# v1_2024-09-18.net
KiCad netlist of a schematic drawn in EasyEDA Pro
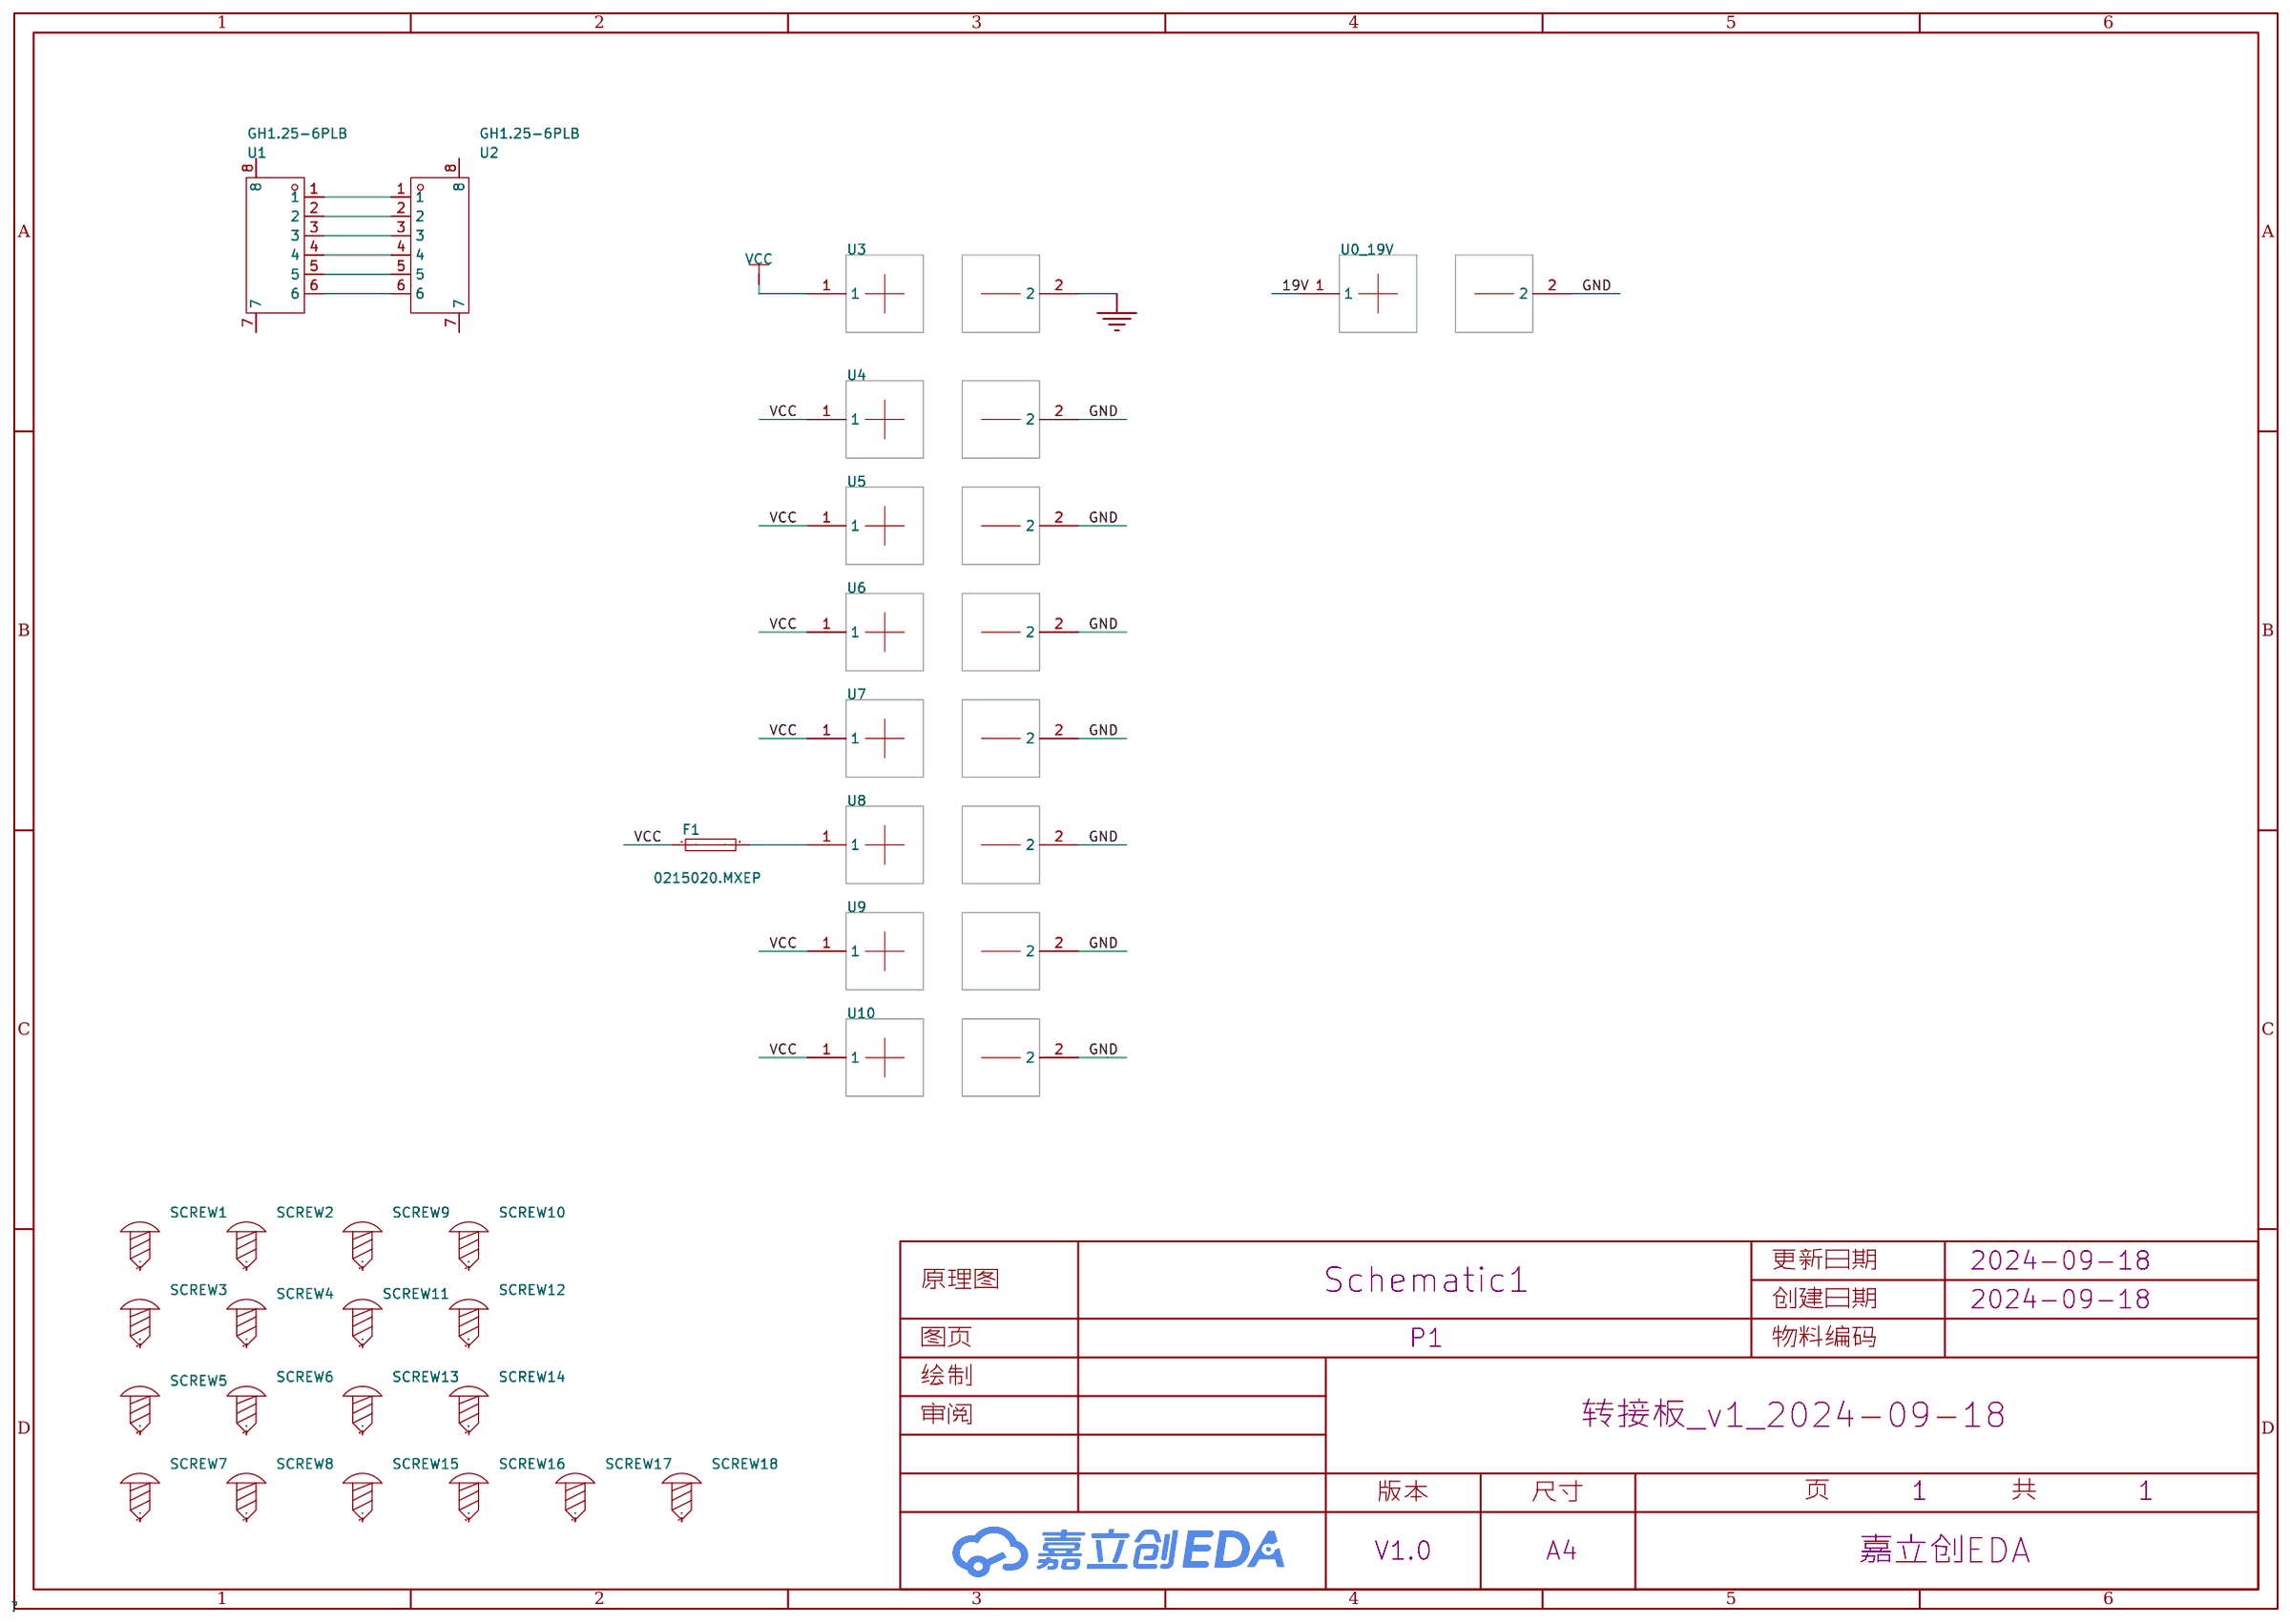
[diagram p0: schematic sheet]

(export (version "E")
  (design (tool "Eeschema 10.0.6"))
  (components
    (comp (ref "F1")
      (value "0215020.MXEP")
      (footprint "easyedapro:FUSE-TH_BD5.5-L21.5-P25.50-D1.2")
      (description "类型:陶瓷管保险丝;额定电流:20A;")
      (fields (field (name "Manufacturer") "Littelfuse(美国力特)"))
      (libsource (lib "easyedapro") (part "0215020.MXEP"))
    )
    (comp (ref "SCREW1")
      (value "~")
      (footprint "easyedapro:M3螺丝")
      (libsource (lib "easyedapro") (part "螺丝孔"))
    )
    (comp (ref "SCREW2")
      (value "~")
      (footprint "easyedapro:M3螺丝")
      (libsource (lib "easyedapro") (part "螺丝孔"))
    )
    (comp (ref "SCREW3")
      (value "~")
      (footprint "easyedapro:M3螺丝")
      (libsource (lib "easyedapro") (part "螺丝孔"))
    )
    (comp (ref "SCREW4")
      (value "~")
      (footprint "easyedapro:M3螺丝")
      (libsource (lib "easyedapro") (part "螺丝孔"))
    )
    (comp (ref "SCREW5")
      (value "~")
      (footprint "easyedapro:M3螺丝")
      (libsource (lib "easyedapro") (part "螺丝孔"))
    )
    (comp (ref "SCREW6")
      (value "~")
      (footprint "easyedapro:M3螺丝")
      (libsource (lib "easyedapro") (part "螺丝孔"))
    )
    (comp (ref "SCREW7")
      (value "~")
      (footprint "easyedapro:M3螺丝")
      (libsource (lib "easyedapro") (part "螺丝孔"))
    )
    (comp (ref "SCREW8")
      (value "~")
      (footprint "easyedapro:M3螺丝")
      (libsource (lib "easyedapro") (part "螺丝孔"))
    )
    (comp (ref "SCREW9")
      (value "~")
      (footprint "easyedapro:M3螺丝")
      (libsource (lib "easyedapro") (part "螺丝孔"))
    )
    (comp (ref "SCREW10")
      (value "~")
      (footprint "easyedapro:M3螺丝")
      (libsource (lib "easyedapro") (part "螺丝孔"))
    )
    (comp (ref "SCREW11")
      (value "~")
      (footprint "easyedapro:M3螺丝")
      (libsource (lib "easyedapro") (part "螺丝孔"))
    )
    (comp (ref "SCREW12")
      (value "~")
      (footprint "easyedapro:M3螺丝")
      (libsource (lib "easyedapro") (part "螺丝孔"))
    )
    (comp (ref "SCREW13")
      (value "~")
      (footprint "easyedapro:M3螺丝")
      (libsource (lib "easyedapro") (part "螺丝孔"))
    )
    (comp (ref "SCREW14")
      (value "~")
      (footprint "easyedapro:M3螺丝")
      (libsource (lib "easyedapro") (part "螺丝孔"))
    )
    (comp (ref "SCREW15")
      (value "~")
      (footprint "easyedapro:M3螺丝")
      (libsource (lib "easyedapro") (part "螺丝孔"))
    )
    (comp (ref "SCREW16")
      (value "~")
      (footprint "easyedapro:M3螺丝")
      (libsource (lib "easyedapro") (part "螺丝孔"))
    )
    (comp (ref "SCREW17")
      (value "~")
      (footprint "easyedapro:M3螺丝")
      (libsource (lib "easyedapro") (part "螺丝孔"))
    )
    (comp (ref "SCREW18")
      (value "~")
      (footprint "easyedapro:M3螺丝")
      (libsource (lib "easyedapro") (part "螺丝孔"))
    )
    (comp (ref "U0_19V") (value "~") (footprint "easyedapro:111") (libsource (lib "easyedapro") (part "111")))
    (comp (ref "U1")
      (value "GH1.25-6PLB")
      (footprint "easyedapro:CONN-SMD_6P-P1.25_XUNPU_WAFER-GH1.25-6PLB")
      (description "插针结构:1x6P;间距:1.25mm;安装方式:立贴;参考系列:GH;总PIN数:6P;排数:1;每排PIN数:6;额定电流:1A;工作温度范围:-25°C~+85°C;")
      (fields (field (name "Manufacturer") "XUNPU(讯普)"))
      (libsource (lib "easyedapro") (part "WAFER-GH1.25-6PLB"))
    )
    (comp (ref "U2")
      (value "GH1.25-6PLB")
      (footprint "easyedapro:CONN-SMD_6P-P1.25_XUNPU_WAFER-GH1.25-6PLB")
      (description "插针结构:1x6P;间距:1.25mm;安装方式:立贴;参考系列:GH;总PIN数:6P;排数:1;每排PIN数:6;额定电流:1A;工作温度范围:-25°C~+85°C;")
      (fields (field (name "Manufacturer") "XUNPU(讯普)"))
      (libsource (lib "easyedapro") (part "WAFER-GH1.25-6PLB"))
    )
    (comp (ref "U3") (value "~") (footprint "easyedapro:111") (libsource (lib "easyedapro") (part "111")))
    (comp (ref "U4") (value "~") (footprint "easyedapro:111") (libsource (lib "easyedapro") (part "111")))
    (comp (ref "U5") (value "~") (footprint "easyedapro:111") (libsource (lib "easyedapro") (part "111")))
    (comp (ref "U6") (value "~") (footprint "easyedapro:111") (libsource (lib "easyedapro") (part "111")))
    (comp (ref "U7") (value "~") (footprint "easyedapro:111") (libsource (lib "easyedapro") (part "111")))
    (comp (ref "U8") (value "~") (footprint "easyedapro:111") (libsource (lib "easyedapro") (part "111")))
    (comp (ref "U9") (value "~") (footprint "easyedapro:111") (libsource (lib "easyedapro") (part "111")))
    (comp (ref "U10") (value "~") (footprint "easyedapro:111") (libsource (lib "easyedapro") (part "111")))
  )
  (nets
    (net (code "1") (name "/19V") (class "Default")
      (node (ref "U0_19V") (pin "1") (pinfunction "1_1") (pintype "input"))
    )
    (net (code "2") (name "GND") (class "Default")
      (node (ref "U0_19V") (pin "2") (pinfunction "2_2") (pintype "input"))
      (node (ref "U10") (pin "2") (pinfunction "2_2") (pintype "input"))
      (node (ref "U3") (pin "2") (pinfunction "2_2") (pintype "input"))
      (node (ref "U4") (pin "2") (pinfunction "2_2") (pintype "input"))
      (node (ref "U5") (pin "2") (pinfunction "2_2") (pintype "input"))
      (node (ref "U6") (pin "2") (pinfunction "2_2") (pintype "input"))
      (node (ref "U7") (pin "2") (pinfunction "2_2") (pintype "input"))
      (node (ref "U8") (pin "2") (pinfunction "2_2") (pintype "input"))
      (node (ref "U9") (pin "2") (pinfunction "2_2") (pintype "input"))
    )
    (net (code "3") (name "Net-(F1-Pad2)") (class "Default")
      (node (ref "F1") (pin "2") (pinfunction "2_2") (pintype "unspecified"))
      (node (ref "U8") (pin "1") (pinfunction "1_1") (pintype "input"))
    )
    (net (code "4") (name "Net-(U1-Pad1)") (class "Default")
      (node (ref "U1") (pin "1") (pinfunction "1_1") (pintype "unspecified"))
      (node (ref "U2") (pin "1") (pinfunction "1_1") (pintype "unspecified"))
    )
    (net (code "5") (name "Net-(U1-Pad2)") (class "Default")
      (node (ref "U1") (pin "2") (pinfunction "2_2") (pintype "unspecified"))
      (node (ref "U2") (pin "2") (pinfunction "2_2") (pintype "unspecified"))
    )
    (net (code "6") (name "Net-(U1-Pad3)") (class "Default")
      (node (ref "U1") (pin "3") (pinfunction "3_3") (pintype "unspecified"))
      (node (ref "U2") (pin "3") (pinfunction "3_3") (pintype "unspecified"))
    )
    (net (code "7") (name "Net-(U1-Pad4)") (class "Default")
      (node (ref "U1") (pin "4") (pinfunction "4_4") (pintype "unspecified"))
      (node (ref "U2") (pin "4") (pinfunction "4_4") (pintype "unspecified"))
    )
    (net (code "8") (name "Net-(U1-Pad5)") (class "Default")
      (node (ref "U1") (pin "5") (pinfunction "5_5") (pintype "unspecified"))
      (node (ref "U2") (pin "5") (pinfunction "5_5") (pintype "unspecified"))
    )
    (net (code "9") (name "Net-(U1-Pad6)") (class "Default")
      (node (ref "U1") (pin "6") (pinfunction "6_6") (pintype "unspecified"))
      (node (ref "U2") (pin "6") (pinfunction "6_6") (pintype "unspecified"))
    )
    (net (code "10") (name "VCC") (class "Default")
      (node (ref "F1") (pin "1") (pinfunction "1_1") (pintype "unspecified"))
      (node (ref "U10") (pin "1") (pinfunction "1_1") (pintype "input"))
      (node (ref "U3") (pin "1") (pinfunction "1_1") (pintype "input"))
      (node (ref "U4") (pin "1") (pinfunction "1_1") (pintype "input"))
      (node (ref "U5") (pin "1") (pinfunction "1_1") (pintype "input"))
      (node (ref "U6") (pin "1") (pinfunction "1_1") (pintype "input"))
      (node (ref "U7") (pin "1") (pinfunction "1_1") (pintype "input"))
      (node (ref "U9") (pin "1") (pinfunction "1_1") (pintype "input"))
    )
    (net (code "11") (name "unconnected-(SCREW1-Pad1)") (class "Default")
      (node (ref "SCREW1") (pin "1") (pinfunction "1_1") (pintype "input"))
    )
    (net (code "12") (name "unconnected-(SCREW2-Pad1)") (class "Default")
      (node (ref "SCREW2") (pin "1") (pinfunction "1_1") (pintype "input"))
    )
    (net (code "13") (name "unconnected-(SCREW3-Pad1)") (class "Default")
      (node (ref "SCREW3") (pin "1") (pinfunction "1_1") (pintype "input"))
    )
    (net (code "14") (name "unconnected-(SCREW4-Pad1)") (class "Default")
      (node (ref "SCREW4") (pin "1") (pinfunction "1_1") (pintype "input"))
    )
    (net (code "15") (name "unconnected-(SCREW5-Pad1)") (class "Default")
      (node (ref "SCREW5") (pin "1") (pinfunction "1_1") (pintype "input"))
    )
    (net (code "16") (name "unconnected-(SCREW6-Pad1)") (class "Default")
      (node (ref "SCREW6") (pin "1") (pinfunction "1_1") (pintype "input"))
    )
    (net (code "17") (name "unconnected-(SCREW7-Pad1)") (class "Default")
      (node (ref "SCREW7") (pin "1") (pinfunction "1_1") (pintype "input"))
    )
    (net (code "18") (name "unconnected-(SCREW8-Pad1)") (class "Default")
      (node (ref "SCREW8") (pin "1") (pinfunction "1_1") (pintype "input"))
    )
    (net (code "19") (name "unconnected-(SCREW9-Pad1)") (class "Default")
      (node (ref "SCREW9") (pin "1") (pinfunction "1_1") (pintype "input"))
    )
    (net (code "20") (name "unconnected-(SCREW10-Pad1)") (class "Default")
      (node (ref "SCREW10") (pin "1") (pinfunction "1_1") (pintype "input"))
    )
    (net (code "21") (name "unconnected-(SCREW11-Pad1)") (class "Default")
      (node (ref "SCREW11") (pin "1") (pinfunction "1_1") (pintype "input"))
    )
    (net (code "22") (name "unconnected-(SCREW12-Pad1)") (class "Default")
      (node (ref "SCREW12") (pin "1") (pinfunction "1_1") (pintype "input"))
    )
    (net (code "23") (name "unconnected-(SCREW13-Pad1)") (class "Default")
      (node (ref "SCREW13") (pin "1") (pinfunction "1_1") (pintype "input"))
    )
    (net (code "24") (name "unconnected-(SCREW14-Pad1)") (class "Default")
      (node (ref "SCREW14") (pin "1") (pinfunction "1_1") (pintype "input"))
    )
    (net (code "25") (name "unconnected-(SCREW15-Pad1)") (class "Default")
      (node (ref "SCREW15") (pin "1") (pinfunction "1_1") (pintype "input"))
    )
    (net (code "26") (name "unconnected-(SCREW16-Pad1)") (class "Default")
      (node (ref "SCREW16") (pin "1") (pinfunction "1_1") (pintype "input"))
    )
    (net (code "27") (name "unconnected-(SCREW17-Pad1)") (class "Default")
      (node (ref "SCREW17") (pin "1") (pinfunction "1_1") (pintype "input"))
    )
    (net (code "28") (name "unconnected-(SCREW18-Pad1)") (class "Default")
      (node (ref "SCREW18") (pin "1") (pinfunction "1_1") (pintype "input"))
    )
    (net (code "29") (name "unconnected-(U1-Pad7)") (class "Default")
      (node (ref "U1") (pin "7") (pinfunction "7_7") (pintype "unspecified"))
    )
    (net (code "30") (name "unconnected-(U1-Pad8)") (class "Default")
      (node (ref "U1") (pin "8") (pinfunction "8_8") (pintype "unspecified"))
    )
    (net (code "31") (name "unconnected-(U2-Pad7)") (class "Default")
      (node (ref "U2") (pin "7") (pinfunction "7_7") (pintype "unspecified"))
    )
    (net (code "32") (name "unconnected-(U2-Pad8)") (class "Default")
      (node (ref "U2") (pin "8") (pinfunction "8_8") (pintype "unspecified"))
    )
  )
)
